# halfbridge_panel.net
KiCad netlist of a schematic drawn in EAGLE
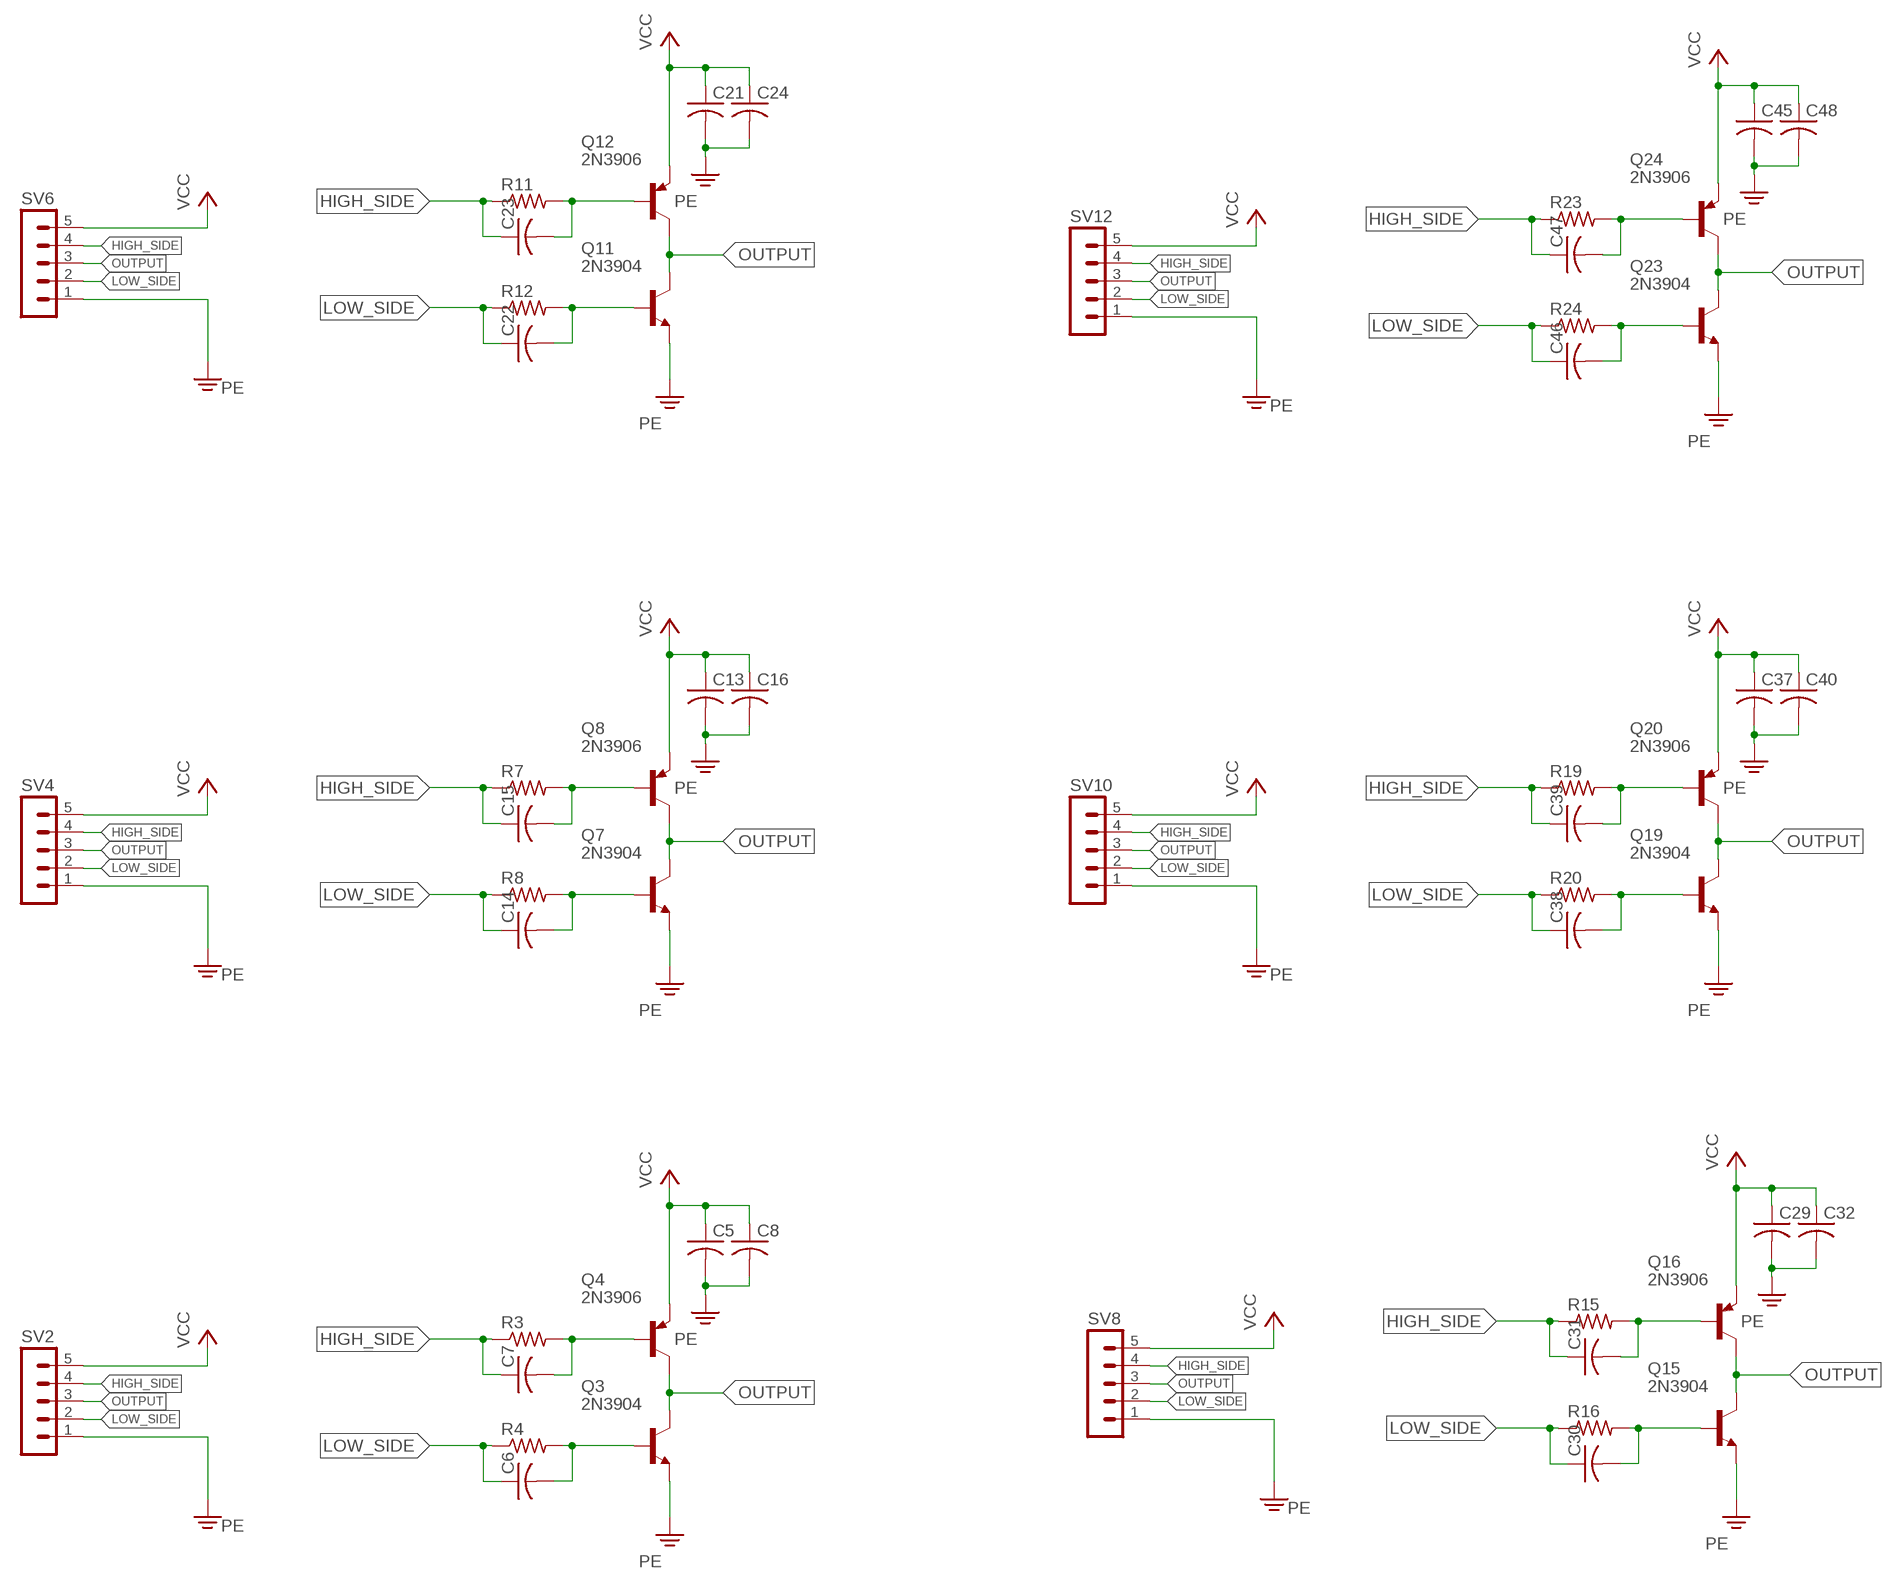
[diagram p0: schematic, sheet 1]

(export (version "E")
  (design (tool "Eeschema 10.0.6"))
  (components
    (comp (ref "C5")
      (value "C-US050-024X044")
      (footprint "eagle-import:C050-024X044")
      (libsource (lib "eagle-import") (part "C-US050-024X044"))
    )
    (comp (ref "C6")
      (value "C-US050-024X044")
      (footprint "eagle-import:C050-024X044")
      (libsource (lib "eagle-import") (part "C-US050-024X044"))
    )
    (comp (ref "C7")
      (value "C-US050-024X044")
      (footprint "eagle-import:C050-024X044")
      (libsource (lib "eagle-import") (part "C-US050-024X044"))
    )
    (comp (ref "C8")
      (value "C-US050-024X044")
      (footprint "eagle-import:C050-024X044")
      (libsource (lib "eagle-import") (part "C-US050-024X044"))
    )
    (comp (ref "C13")
      (value "C-US050-024X044")
      (footprint "eagle-import:C050-024X044")
      (libsource (lib "eagle-import") (part "C-US050-024X044"))
    )
    (comp (ref "C14")
      (value "C-US050-024X044")
      (footprint "eagle-import:C050-024X044")
      (libsource (lib "eagle-import") (part "C-US050-024X044"))
    )
    (comp (ref "C15")
      (value "C-US050-024X044")
      (footprint "eagle-import:C050-024X044")
      (libsource (lib "eagle-import") (part "C-US050-024X044"))
    )
    (comp (ref "C16")
      (value "C-US050-024X044")
      (footprint "eagle-import:C050-024X044")
      (libsource (lib "eagle-import") (part "C-US050-024X044"))
    )
    (comp (ref "C21")
      (value "C-US050-024X044")
      (footprint "eagle-import:C050-024X044")
      (libsource (lib "eagle-import") (part "C-US050-024X044"))
    )
    (comp (ref "C22")
      (value "C-US050-024X044")
      (footprint "eagle-import:C050-024X044")
      (libsource (lib "eagle-import") (part "C-US050-024X044"))
    )
    (comp (ref "C23")
      (value "C-US050-024X044")
      (footprint "eagle-import:C050-024X044")
      (libsource (lib "eagle-import") (part "C-US050-024X044"))
    )
    (comp (ref "C24")
      (value "C-US050-024X044")
      (footprint "eagle-import:C050-024X044")
      (libsource (lib "eagle-import") (part "C-US050-024X044"))
    )
    (comp (ref "C29")
      (value "C-US050-024X044")
      (footprint "eagle-import:C050-024X044")
      (libsource (lib "eagle-import") (part "C-US050-024X044"))
    )
    (comp (ref "C30")
      (value "C-US050-024X044")
      (footprint "eagle-import:C050-024X044")
      (libsource (lib "eagle-import") (part "C-US050-024X044"))
    )
    (comp (ref "C31")
      (value "C-US050-024X044")
      (footprint "eagle-import:C050-024X044")
      (libsource (lib "eagle-import") (part "C-US050-024X044"))
    )
    (comp (ref "C32")
      (value "C-US050-024X044")
      (footprint "eagle-import:C050-024X044")
      (libsource (lib "eagle-import") (part "C-US050-024X044"))
    )
    (comp (ref "C37")
      (value "C-US050-024X044")
      (footprint "eagle-import:C050-024X044")
      (libsource (lib "eagle-import") (part "C-US050-024X044"))
    )
    (comp (ref "C38")
      (value "C-US050-024X044")
      (footprint "eagle-import:C050-024X044")
      (libsource (lib "eagle-import") (part "C-US050-024X044"))
    )
    (comp (ref "C39")
      (value "C-US050-024X044")
      (footprint "eagle-import:C050-024X044")
      (libsource (lib "eagle-import") (part "C-US050-024X044"))
    )
    (comp (ref "C40")
      (value "C-US050-024X044")
      (footprint "eagle-import:C050-024X044")
      (libsource (lib "eagle-import") (part "C-US050-024X044"))
    )
    (comp (ref "C45")
      (value "C-US050-024X044")
      (footprint "eagle-import:C050-024X044")
      (libsource (lib "eagle-import") (part "C-US050-024X044"))
    )
    (comp (ref "C46")
      (value "C-US050-024X044")
      (footprint "eagle-import:C050-024X044")
      (libsource (lib "eagle-import") (part "C-US050-024X044"))
    )
    (comp (ref "C47")
      (value "C-US050-024X044")
      (footprint "eagle-import:C050-024X044")
      (libsource (lib "eagle-import") (part "C-US050-024X044"))
    )
    (comp (ref "C48")
      (value "C-US050-024X044")
      (footprint "eagle-import:C050-024X044")
      (libsource (lib "eagle-import") (part "C-US050-024X044"))
    )
    (comp (ref "Q3")
      (value "2N3904")
      (footprint "eagle-import:TO-92")
      (libsource (lib "eagle-import") (part "2N3904"))
    )
    (comp (ref "Q4")
      (value "2N3906")
      (footprint "eagle-import:TO-92")
      (libsource (lib "eagle-import") (part "2N3906"))
    )
    (comp (ref "Q7")
      (value "2N3904")
      (footprint "eagle-import:TO-92")
      (libsource (lib "eagle-import") (part "2N3904"))
    )
    (comp (ref "Q8")
      (value "2N3906")
      (footprint "eagle-import:TO-92")
      (libsource (lib "eagle-import") (part "2N3906"))
    )
    (comp (ref "Q11")
      (value "2N3904")
      (footprint "eagle-import:TO-92")
      (libsource (lib "eagle-import") (part "2N3904"))
    )
    (comp (ref "Q12")
      (value "2N3906")
      (footprint "eagle-import:TO-92")
      (libsource (lib "eagle-import") (part "2N3906"))
    )
    (comp (ref "Q15")
      (value "2N3904")
      (footprint "eagle-import:TO-92")
      (libsource (lib "eagle-import") (part "2N3904"))
    )
    (comp (ref "Q16")
      (value "2N3906")
      (footprint "eagle-import:TO-92")
      (libsource (lib "eagle-import") (part "2N3906"))
    )
    (comp (ref "Q19")
      (value "2N3904")
      (footprint "eagle-import:TO-92")
      (libsource (lib "eagle-import") (part "2N3904"))
    )
    (comp (ref "Q20")
      (value "2N3906")
      (footprint "eagle-import:TO-92")
      (libsource (lib "eagle-import") (part "2N3906"))
    )
    (comp (ref "Q23")
      (value "2N3904")
      (footprint "eagle-import:TO-92")
      (libsource (lib "eagle-import") (part "2N3904"))
    )
    (comp (ref "Q24")
      (value "2N3906")
      (footprint "eagle-import:TO-92")
      (libsource (lib "eagle-import") (part "2N3906"))
    )
    (comp (ref "R3")
      (value "R-US_0204/5")
      (footprint "eagle-import:0204_5")
      (libsource (lib "eagle-import") (part "R-US_0204/5"))
    )
    (comp (ref "R4")
      (value "R-US_0204/5")
      (footprint "eagle-import:0204_5")
      (libsource (lib "eagle-import") (part "R-US_0204/5"))
    )
    (comp (ref "R7")
      (value "R-US_0204/5")
      (footprint "eagle-import:0204_5")
      (libsource (lib "eagle-import") (part "R-US_0204/5"))
    )
    (comp (ref "R8")
      (value "R-US_0204/5")
      (footprint "eagle-import:0204_5")
      (libsource (lib "eagle-import") (part "R-US_0204/5"))
    )
    (comp (ref "R11")
      (value "R-US_0204/5")
      (footprint "eagle-import:0204_5")
      (libsource (lib "eagle-import") (part "R-US_0204/5"))
    )
    (comp (ref "R12")
      (value "R-US_0204/5")
      (footprint "eagle-import:0204_5")
      (libsource (lib "eagle-import") (part "R-US_0204/5"))
    )
    (comp (ref "R15")
      (value "R-US_0204/5")
      (footprint "eagle-import:0204_5")
      (libsource (lib "eagle-import") (part "R-US_0204/5"))
    )
    (comp (ref "R16")
      (value "R-US_0204/5")
      (footprint "eagle-import:0204_5")
      (libsource (lib "eagle-import") (part "R-US_0204/5"))
    )
    (comp (ref "R19")
      (value "R-US_0204/5")
      (footprint "eagle-import:0204_5")
      (libsource (lib "eagle-import") (part "R-US_0204/5"))
    )
    (comp (ref "R20")
      (value "R-US_0204/5")
      (footprint "eagle-import:0204_5")
      (libsource (lib "eagle-import") (part "R-US_0204/5"))
    )
    (comp (ref "R23")
      (value "R-US_0204/5")
      (footprint "eagle-import:0204_5")
      (libsource (lib "eagle-import") (part "R-US_0204/5"))
    )
    (comp (ref "R24")
      (value "R-US_0204/5")
      (footprint "eagle-import:0204_5")
      (libsource (lib "eagle-import") (part "R-US_0204/5"))
    )
    (comp (ref "SV2")
      (value "MA05-1")
      (footprint "eagle-import:MA05-1")
      (libsource (lib "eagle-import") (part "MA05-1"))
    )
    (comp (ref "SV4")
      (value "MA05-1")
      (footprint "eagle-import:MA05-1")
      (libsource (lib "eagle-import") (part "MA05-1"))
    )
    (comp (ref "SV6")
      (value "MA05-1")
      (footprint "eagle-import:MA05-1")
      (libsource (lib "eagle-import") (part "MA05-1"))
    )
    (comp (ref "SV8")
      (value "MA05-1")
      (footprint "eagle-import:MA05-1")
      (libsource (lib "eagle-import") (part "MA05-1"))
    )
    (comp (ref "SV10")
      (value "MA05-1")
      (footprint "eagle-import:MA05-1")
      (libsource (lib "eagle-import") (part "MA05-1"))
    )
    (comp (ref "SV12")
      (value "MA05-1")
      (footprint "eagle-import:MA05-1")
      (libsource (lib "eagle-import") (part "MA05-1"))
    )
  )
  (nets
    (net (code "1") (name "HIGH_SIDE") (class "Default")
      (node (ref "C15") (pin "1") (pinfunction "1_1") (pintype "passive"))
      (node (ref "C23") (pin "1") (pinfunction "1_1") (pintype "passive"))
      (node (ref "C31") (pin "1") (pinfunction "1_1") (pintype "passive"))
      (node (ref "C39") (pin "1") (pinfunction "1_1") (pintype "passive"))
      (node (ref "C47") (pin "1") (pinfunction "1_1") (pintype "passive"))
      (node (ref "C7") (pin "1") (pinfunction "1_1") (pintype "passive"))
      (node (ref "R11") (pin "1") (pinfunction "1_1") (pintype "passive"))
      (node (ref "R15") (pin "1") (pinfunction "1_1") (pintype "passive"))
      (node (ref "R19") (pin "1") (pinfunction "1_1") (pintype "passive"))
      (node (ref "R23") (pin "1") (pinfunction "1_1") (pintype "passive"))
      (node (ref "R3") (pin "1") (pinfunction "1_1") (pintype "passive"))
      (node (ref "R7") (pin "1") (pinfunction "1_1") (pintype "passive"))
      (node (ref "SV10") (pin "4") (pinfunction "4_4") (pintype "passive"))
      (node (ref "SV12") (pin "4") (pinfunction "4_4") (pintype "passive"))
      (node (ref "SV2") (pin "4") (pinfunction "4_4") (pintype "passive"))
      (node (ref "SV4") (pin "4") (pinfunction "4_4") (pintype "passive"))
      (node (ref "SV6") (pin "4") (pinfunction "4_4") (pintype "passive"))
      (node (ref "SV8") (pin "4") (pinfunction "4_4") (pintype "passive"))
    )
    (net (code "2") (name "LOW_SIDE") (class "Default")
      (node (ref "C14") (pin "1") (pinfunction "1_1") (pintype "passive"))
      (node (ref "C22") (pin "1") (pinfunction "1_1") (pintype "passive"))
      (node (ref "C30") (pin "1") (pinfunction "1_1") (pintype "passive"))
      (node (ref "C38") (pin "1") (pinfunction "1_1") (pintype "passive"))
      (node (ref "C46") (pin "1") (pinfunction "1_1") (pintype "passive"))
      (node (ref "C6") (pin "1") (pinfunction "1_1") (pintype "passive"))
      (node (ref "R12") (pin "1") (pinfunction "1_1") (pintype "passive"))
      (node (ref "R16") (pin "1") (pinfunction "1_1") (pintype "passive"))
      (node (ref "R20") (pin "1") (pinfunction "1_1") (pintype "passive"))
      (node (ref "R24") (pin "1") (pinfunction "1_1") (pintype "passive"))
      (node (ref "R4") (pin "1") (pinfunction "1_1") (pintype "passive"))
      (node (ref "R8") (pin "1") (pinfunction "1_1") (pintype "passive"))
      (node (ref "SV10") (pin "2") (pinfunction "2_2") (pintype "passive"))
      (node (ref "SV12") (pin "2") (pinfunction "2_2") (pintype "passive"))
      (node (ref "SV2") (pin "2") (pinfunction "2_2") (pintype "passive"))
      (node (ref "SV4") (pin "2") (pinfunction "2_2") (pintype "passive"))
      (node (ref "SV6") (pin "2") (pinfunction "2_2") (pintype "passive"))
      (node (ref "SV8") (pin "2") (pinfunction "2_2") (pintype "passive"))
    )
    (net (code "3") (name "Net-(C6-Pad2)") (class "Default")
      (node (ref "C6") (pin "2") (pinfunction "2_2") (pintype "passive"))
      (node (ref "Q3") (pin "B") (pinfunction "B_B") (pintype "passive"))
      (node (ref "R4") (pin "2") (pinfunction "2_2") (pintype "passive"))
    )
    (net (code "4") (name "Net-(C7-Pad2)") (class "Default")
      (node (ref "C7") (pin "2") (pinfunction "2_2") (pintype "passive"))
      (node (ref "Q4") (pin "B") (pinfunction "B_B") (pintype "passive"))
      (node (ref "R3") (pin "2") (pinfunction "2_2") (pintype "passive"))
    )
    (net (code "5") (name "Net-(C14-Pad2)") (class "Default")
      (node (ref "C14") (pin "2") (pinfunction "2_2") (pintype "passive"))
      (node (ref "Q7") (pin "B") (pinfunction "B_B") (pintype "passive"))
      (node (ref "R8") (pin "2") (pinfunction "2_2") (pintype "passive"))
    )
    (net (code "6") (name "Net-(C15-Pad2)") (class "Default")
      (node (ref "C15") (pin "2") (pinfunction "2_2") (pintype "passive"))
      (node (ref "Q8") (pin "B") (pinfunction "B_B") (pintype "passive"))
      (node (ref "R7") (pin "2") (pinfunction "2_2") (pintype "passive"))
    )
    (net (code "7") (name "Net-(C22-Pad2)") (class "Default")
      (node (ref "C22") (pin "2") (pinfunction "2_2") (pintype "passive"))
      (node (ref "Q11") (pin "B") (pinfunction "B_B") (pintype "passive"))
      (node (ref "R12") (pin "2") (pinfunction "2_2") (pintype "passive"))
    )
    (net (code "8") (name "Net-(C23-Pad2)") (class "Default")
      (node (ref "C23") (pin "2") (pinfunction "2_2") (pintype "passive"))
      (node (ref "Q12") (pin "B") (pinfunction "B_B") (pintype "passive"))
      (node (ref "R11") (pin "2") (pinfunction "2_2") (pintype "passive"))
    )
    (net (code "9") (name "Net-(C30-Pad2)") (class "Default")
      (node (ref "C30") (pin "2") (pinfunction "2_2") (pintype "passive"))
      (node (ref "Q15") (pin "B") (pinfunction "B_B") (pintype "passive"))
      (node (ref "R16") (pin "2") (pinfunction "2_2") (pintype "passive"))
    )
    (net (code "10") (name "Net-(C31-Pad2)") (class "Default")
      (node (ref "C31") (pin "2") (pinfunction "2_2") (pintype "passive"))
      (node (ref "Q16") (pin "B") (pinfunction "B_B") (pintype "passive"))
      (node (ref "R15") (pin "2") (pinfunction "2_2") (pintype "passive"))
    )
    (net (code "11") (name "Net-(C38-Pad2)") (class "Default")
      (node (ref "C38") (pin "2") (pinfunction "2_2") (pintype "passive"))
      (node (ref "Q19") (pin "B") (pinfunction "B_B") (pintype "passive"))
      (node (ref "R20") (pin "2") (pinfunction "2_2") (pintype "passive"))
    )
    (net (code "12") (name "Net-(C39-Pad2)") (class "Default")
      (node (ref "C39") (pin "2") (pinfunction "2_2") (pintype "passive"))
      (node (ref "Q20") (pin "B") (pinfunction "B_B") (pintype "passive"))
      (node (ref "R19") (pin "2") (pinfunction "2_2") (pintype "passive"))
    )
    (net (code "13") (name "Net-(C46-Pad2)") (class "Default")
      (node (ref "C46") (pin "2") (pinfunction "2_2") (pintype "passive"))
      (node (ref "Q23") (pin "B") (pinfunction "B_B") (pintype "passive"))
      (node (ref "R24") (pin "2") (pinfunction "2_2") (pintype "passive"))
    )
    (net (code "14") (name "Net-(C47-Pad2)") (class "Default")
      (node (ref "C47") (pin "2") (pinfunction "2_2") (pintype "passive"))
      (node (ref "Q24") (pin "B") (pinfunction "B_B") (pintype "passive"))
      (node (ref "R23") (pin "2") (pinfunction "2_2") (pintype "passive"))
    )
    (net (code "15") (name "OUTPUT") (class "Default")
      (node (ref "Q11") (pin "C") (pinfunction "C_C") (pintype "passive"))
      (node (ref "Q12") (pin "C") (pinfunction "C_C") (pintype "passive"))
      (node (ref "Q15") (pin "C") (pinfunction "C_C") (pintype "passive"))
      (node (ref "Q16") (pin "C") (pinfunction "C_C") (pintype "passive"))
      (node (ref "Q19") (pin "C") (pinfunction "C_C") (pintype "passive"))
      (node (ref "Q20") (pin "C") (pinfunction "C_C") (pintype "passive"))
      (node (ref "Q23") (pin "C") (pinfunction "C_C") (pintype "passive"))
      (node (ref "Q24") (pin "C") (pinfunction "C_C") (pintype "passive"))
      (node (ref "Q3") (pin "C") (pinfunction "C_C") (pintype "passive"))
      (node (ref "Q4") (pin "C") (pinfunction "C_C") (pintype "passive"))
      (node (ref "Q7") (pin "C") (pinfunction "C_C") (pintype "passive"))
      (node (ref "Q8") (pin "C") (pinfunction "C_C") (pintype "passive"))
      (node (ref "SV10") (pin "3") (pinfunction "3_3") (pintype "passive"))
      (node (ref "SV12") (pin "3") (pinfunction "3_3") (pintype "passive"))
      (node (ref "SV2") (pin "3") (pinfunction "3_3") (pintype "passive"))
      (node (ref "SV4") (pin "3") (pinfunction "3_3") (pintype "passive"))
      (node (ref "SV6") (pin "3") (pinfunction "3_3") (pintype "passive"))
      (node (ref "SV8") (pin "3") (pinfunction "3_3") (pintype "passive"))
    )
    (net (code "16") (name "PE") (class "Default")
      (node (ref "C13") (pin "2") (pinfunction "2_2") (pintype "passive"))
      (node (ref "C16") (pin "2") (pinfunction "2_2") (pintype "passive"))
      (node (ref "C21") (pin "2") (pinfunction "2_2") (pintype "passive"))
      (node (ref "C24") (pin "2") (pinfunction "2_2") (pintype "passive"))
      (node (ref "C29") (pin "2") (pinfunction "2_2") (pintype "passive"))
      (node (ref "C32") (pin "2") (pinfunction "2_2") (pintype "passive"))
      (node (ref "C37") (pin "2") (pinfunction "2_2") (pintype "passive"))
      (node (ref "C40") (pin "2") (pinfunction "2_2") (pintype "passive"))
      (node (ref "C45") (pin "2") (pinfunction "2_2") (pintype "passive"))
      (node (ref "C48") (pin "2") (pinfunction "2_2") (pintype "passive"))
      (node (ref "C5") (pin "2") (pinfunction "2_2") (pintype "passive"))
      (node (ref "C8") (pin "2") (pinfunction "2_2") (pintype "passive"))
      (node (ref "Q11") (pin "E") (pinfunction "E_E") (pintype "passive"))
      (node (ref "Q15") (pin "E") (pinfunction "E_E") (pintype "passive"))
      (node (ref "Q19") (pin "E") (pinfunction "E_E") (pintype "passive"))
      (node (ref "Q23") (pin "E") (pinfunction "E_E") (pintype "passive"))
      (node (ref "Q3") (pin "E") (pinfunction "E_E") (pintype "passive"))
      (node (ref "Q7") (pin "E") (pinfunction "E_E") (pintype "passive"))
      (node (ref "SV10") (pin "1") (pinfunction "1_1") (pintype "passive"))
      (node (ref "SV12") (pin "1") (pinfunction "1_1") (pintype "passive"))
      (node (ref "SV2") (pin "1") (pinfunction "1_1") (pintype "passive"))
      (node (ref "SV4") (pin "1") (pinfunction "1_1") (pintype "passive"))
      (node (ref "SV6") (pin "1") (pinfunction "1_1") (pintype "passive"))
      (node (ref "SV8") (pin "1") (pinfunction "1_1") (pintype "passive"))
    )
    (net (code "17") (name "VCC") (class "Default")
      (node (ref "C13") (pin "1") (pinfunction "1_1") (pintype "passive"))
      (node (ref "C16") (pin "1") (pinfunction "1_1") (pintype "passive"))
      (node (ref "C21") (pin "1") (pinfunction "1_1") (pintype "passive"))
      (node (ref "C24") (pin "1") (pinfunction "1_1") (pintype "passive"))
      (node (ref "C29") (pin "1") (pinfunction "1_1") (pintype "passive"))
      (node (ref "C32") (pin "1") (pinfunction "1_1") (pintype "passive"))
      (node (ref "C37") (pin "1") (pinfunction "1_1") (pintype "passive"))
      (node (ref "C40") (pin "1") (pinfunction "1_1") (pintype "passive"))
      (node (ref "C45") (pin "1") (pinfunction "1_1") (pintype "passive"))
      (node (ref "C48") (pin "1") (pinfunction "1_1") (pintype "passive"))
      (node (ref "C5") (pin "1") (pinfunction "1_1") (pintype "passive"))
      (node (ref "C8") (pin "1") (pinfunction "1_1") (pintype "passive"))
      (node (ref "Q12") (pin "E") (pinfunction "E_E") (pintype "passive"))
      (node (ref "Q16") (pin "E") (pinfunction "E_E") (pintype "passive"))
      (node (ref "Q20") (pin "E") (pinfunction "E_E") (pintype "passive"))
      (node (ref "Q24") (pin "E") (pinfunction "E_E") (pintype "passive"))
      (node (ref "Q4") (pin "E") (pinfunction "E_E") (pintype "passive"))
      (node (ref "Q8") (pin "E") (pinfunction "E_E") (pintype "passive"))
      (node (ref "SV10") (pin "5") (pinfunction "5_5") (pintype "passive"))
      (node (ref "SV12") (pin "5") (pinfunction "5_5") (pintype "passive"))
      (node (ref "SV2") (pin "5") (pinfunction "5_5") (pintype "passive"))
      (node (ref "SV4") (pin "5") (pinfunction "5_5") (pintype "passive"))
      (node (ref "SV6") (pin "5") (pinfunction "5_5") (pintype "passive"))
      (node (ref "SV8") (pin "5") (pinfunction "5_5") (pintype "passive"))
    )
  )
)
